# JoyStickAdcInput.net
KiCad netlist of a schematic drawn in Altium Designer
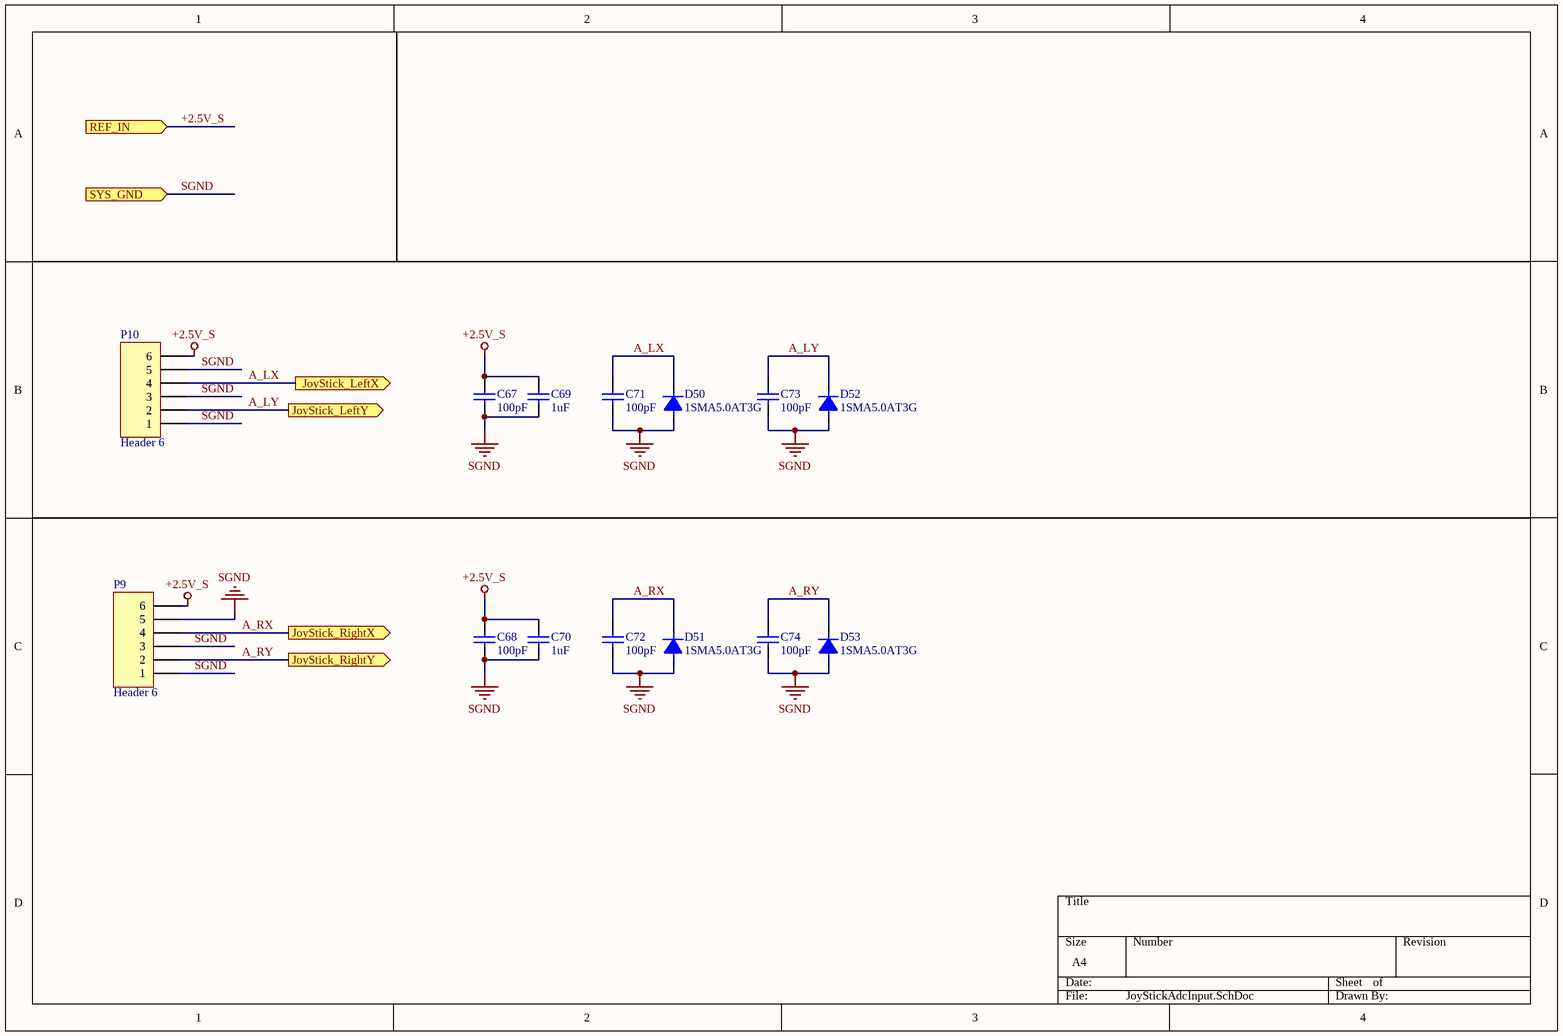
[diagram p0: JoyStickAdcInput.SchDoc]

(export (version "E")
  (design (tool "Eeschema 10.0.6"))
  (components
    (comp (ref "C67")
      (value "100pF")
      (footprint "C0805")
      (description "Capacitor")
      (fields (field (name "PUBLISHER") "Altium Limited"))
      (libsource (lib "Miscellaneous Devices") (part "Cap"))
    )
    (comp (ref "C68")
      (value "100pF")
      (footprint "C0805")
      (description "Capacitor")
      (fields (field (name "PUBLISHER") "Altium Limited"))
      (libsource (lib "Miscellaneous Devices") (part "Cap"))
    )
    (comp (ref "C69")
      (value "1uF")
      (footprint "C0805")
      (description "Capacitor")
      (fields (field (name "PUBLISHER") "Altium Limited"))
      (libsource (lib "Miscellaneous Devices") (part "Cap"))
    )
    (comp (ref "C70")
      (value "1uF")
      (footprint "C0805")
      (description "Capacitor")
      (fields (field (name "PUBLISHER") "Altium Limited"))
      (libsource (lib "Miscellaneous Devices") (part "Cap"))
    )
    (comp (ref "C71")
      (value "100pF")
      (footprint "C0805")
      (description "Capacitor")
      (fields (field (name "PUBLISHER") "Altium Limited"))
      (libsource (lib "Miscellaneous Devices") (part "Cap"))
    )
    (comp (ref "C72")
      (value "100pF")
      (footprint "C0805")
      (description "Capacitor")
      (fields (field (name "PUBLISHER") "Altium Limited"))
      (libsource (lib "Miscellaneous Devices") (part "Cap"))
    )
    (comp (ref "C73")
      (value "100pF")
      (footprint "C0805")
      (description "Capacitor")
      (fields (field (name "PUBLISHER") "Altium Limited"))
      (libsource (lib "Miscellaneous Devices") (part "Cap"))
    )
    (comp (ref "C74")
      (value "100pF")
      (footprint "C0805")
      (description "Capacitor")
      (fields (field (name "PUBLISHER") "Altium Limited"))
      (libsource (lib "Miscellaneous Devices") (part "Cap"))
    )
    (comp (ref "D50")
      (value "1SMA5.0AT3G")
      (footprint "SMA")
      (description "Diode")
      (libsource (lib "*") (part "DIODE1"))
    )
    (comp (ref "D51")
      (value "1SMA5.0AT3G")
      (footprint "SMA")
      (description "Diode")
      (libsource (lib "*") (part "DIODE1"))
    )
    (comp (ref "D52")
      (value "1SMA5.0AT3G")
      (footprint "SMA")
      (description "Diode")
      (libsource (lib "*") (part "DIODE1"))
    )
    (comp (ref "D53")
      (value "1SMA5.0AT3G")
      (footprint "SMA")
      (description "Diode")
      (libsource (lib "*") (part "DIODE1"))
    )
    (comp (ref "P9")
      (value "Header 6")
      (footprint "FFC/SM1.0-6")
      (description "Header, 6-Pin")
      (fields (field (name "PUBLISHER") "Altium Limited"))
      (libsource (lib "Miscellaneous Connectors") (part "Header 6"))
    )
    (comp (ref "P10")
      (value "Header 6")
      (footprint "FFC/SM1.0-6")
      (description "Header, 6-Pin")
      (fields (field (name "PUBLISHER") "Altium Limited"))
      (libsource (lib "Miscellaneous Connectors") (part "Header 6"))
    )
  )
  (nets
    (net (code "1") (name "+2.5V_S") (class "Default")
      (node (ref "C67") (pin "1") (pinfunction "1_1") (pintype "passive"))
      (node (ref "C68") (pin "1") (pinfunction "1_1") (pintype "passive"))
      (node (ref "C69") (pin "1") (pinfunction "1_1") (pintype "passive"))
      (node (ref "C70") (pin "1") (pinfunction "1_1") (pintype "passive"))
      (node (ref "P10") (pin "6") (pinfunction "6_6") (pintype "passive"))
      (node (ref "P9") (pin "6") (pinfunction "6_6") (pintype "passive"))
    )
    (net (code "2") (name "/A_LX") (class "Default")
      (node (ref "C71") (pin "1") (pinfunction "1_1") (pintype "passive"))
      (node (ref "D50") (pin "2") (pinfunction "K_2") (pintype "passive"))
      (node (ref "P10") (pin "4") (pinfunction "4_4") (pintype "passive"))
    )
    (net (code "3") (name "/A_LY") (class "Default")
      (node (ref "C73") (pin "1") (pinfunction "1_1") (pintype "passive"))
      (node (ref "D52") (pin "2") (pinfunction "K_2") (pintype "passive"))
      (node (ref "P10") (pin "2") (pinfunction "2_2") (pintype "passive"))
    )
    (net (code "4") (name "/A_RX") (class "Default")
      (node (ref "C72") (pin "1") (pinfunction "1_1") (pintype "passive"))
      (node (ref "D51") (pin "2") (pinfunction "K_2") (pintype "passive"))
      (node (ref "P9") (pin "4") (pinfunction "4_4") (pintype "passive"))
    )
    (net (code "5") (name "/A_RY") (class "Default")
      (node (ref "C74") (pin "1") (pinfunction "1_1") (pintype "passive"))
      (node (ref "D53") (pin "2") (pinfunction "K_2") (pintype "passive"))
      (node (ref "P9") (pin "2") (pinfunction "2_2") (pintype "passive"))
    )
    (net (code "6") (name "SGND") (class "Default")
      (node (ref "C67") (pin "2") (pinfunction "2_2") (pintype "passive"))
      (node (ref "C68") (pin "2") (pinfunction "2_2") (pintype "passive"))
      (node (ref "C69") (pin "2") (pinfunction "2_2") (pintype "passive"))
      (node (ref "C70") (pin "2") (pinfunction "2_2") (pintype "passive"))
      (node (ref "C71") (pin "2") (pinfunction "2_2") (pintype "passive"))
      (node (ref "C72") (pin "2") (pinfunction "2_2") (pintype "passive"))
      (node (ref "C73") (pin "2") (pinfunction "2_2") (pintype "passive"))
      (node (ref "C74") (pin "2") (pinfunction "2_2") (pintype "passive"))
      (node (ref "D50") (pin "1") (pinfunction "A_1") (pintype "passive"))
      (node (ref "D51") (pin "1") (pinfunction "A_1") (pintype "passive"))
      (node (ref "D52") (pin "1") (pinfunction "A_1") (pintype "passive"))
      (node (ref "D53") (pin "1") (pinfunction "A_1") (pintype "passive"))
      (node (ref "P10") (pin "1") (pinfunction "1_1") (pintype "passive"))
      (node (ref "P10") (pin "3") (pinfunction "3_3") (pintype "passive"))
      (node (ref "P10") (pin "5") (pinfunction "5_5") (pintype "passive"))
      (node (ref "P9") (pin "1") (pinfunction "1_1") (pintype "passive"))
      (node (ref "P9") (pin "3") (pinfunction "3_3") (pintype "passive"))
      (node (ref "P9") (pin "5") (pinfunction "5_5") (pintype "passive"))
    )
  )
)
